# USB-PORT.net
KiCad netlist of a schematic drawn in Altium Designer
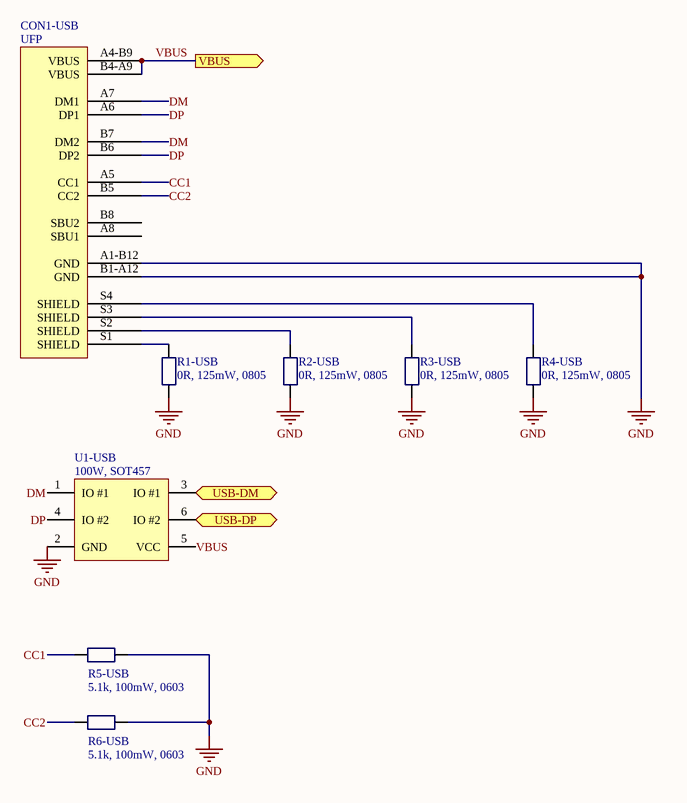
[diagram p0: USB-PORT.SchDoc]

(export (version "E")
  (design (tool "Eeschema 10.0.6"))
  (components
    (comp (ref "CON1-USB")
      (value "UFP")
      (footprint "Molex USB Type-C")
      (description "USB Connector, USB Type C, USB 2.0, Receptacle, 16 Ways, Surface Mount, Right Angle")
      (fields (field (name "MANUFACTURER") "MOLEX"))
      (libsource (lib "SCH-LIB") (part "Molex USB 2.0 Type-C Receptacle"))
    )
    (comp (ref "R1-USB")
      (value "0R, 125mW, 0805")
      (footprint "0805 [2012]")
      (fields (field (name "MANUFACTURER") "MULTICOMP PRO"))
      (libsource (lib "SCH-LIB") (part "Resistor"))
    )
    (comp (ref "R2-USB")
      (value "0R, 125mW, 0805")
      (footprint "0805 [2012]")
      (fields (field (name "MANUFACTURER") "MULTICOMP PRO"))
      (libsource (lib "SCH-LIB") (part "Resistor"))
    )
    (comp (ref "R3-USB")
      (value "0R, 125mW, 0805")
      (footprint "0805 [2012]")
      (fields (field (name "MANUFACTURER") "MULTICOMP PRO"))
      (libsource (lib "SCH-LIB") (part "Resistor"))
    )
    (comp (ref "R4-USB")
      (value "0R, 125mW, 0805")
      (footprint "0805 [2012]")
      (fields (field (name "MANUFACTURER") "MULTICOMP PRO"))
      (libsource (lib "SCH-LIB") (part "Resistor"))
    )
    (comp (ref "R5-USB")
      (value "5.1k, 100mW, 0603")
      (footprint "0603 [1608]")
      (fields (field (name "MANUFACTURER") "YAGEO"))
      (libsource (lib "SCH-LIB") (part "Resistor"))
    )
    (comp (ref "R6-USB")
      (value "5.1k, 100mW, 0603")
      (footprint "0603 [1608]")
      (fields (field (name "MANUFACTURER") "YAGEO"))
      (libsource (lib "SCH-LIB") (part "Resistor"))
    )
    (comp (ref "U1-USB")
      (value "100W, SOT457")
      (footprint "SOT457")
      (fields (field (name "MANUFACTURER") "NEXPERIA"))
      (libsource (lib "SCH-LIB") (part "ESD Protection Device"))
    )
  )
  (nets
    (net (code "1") (name "/CC1") (class "Default")
      (node (ref "CON1-USB") (pin "A5") (pinfunction "CC1_A5") (pintype "passive"))
      (node (ref "R5-USB") (pin "2") (pinfunction "2_2") (pintype "passive"))
    )
    (net (code "2") (name "/CC2") (class "Default")
      (node (ref "CON1-USB") (pin "B5") (pinfunction "CC2_B5") (pintype "passive"))
      (node (ref "R6-USB") (pin "2") (pinfunction "2_2") (pintype "passive"))
    )
    (net (code "3") (name "/DM") (class "Default")
      (node (ref "CON1-USB") (pin "A7") (pinfunction "DM1_A7") (pintype "passive"))
      (node (ref "CON1-USB") (pin "B7") (pinfunction "DM2_B7") (pintype "passive"))
      (node (ref "U1-USB") (pin "1") (pinfunction "IO_#1_1") (pintype "passive"))
    )
    (net (code "4") (name "/DP") (class "Default")
      (node (ref "CON1-USB") (pin "A6") (pinfunction "DP1_A6") (pintype "passive"))
      (node (ref "CON1-USB") (pin "B6") (pinfunction "DP2_B6") (pintype "passive"))
      (node (ref "U1-USB") (pin "4") (pinfunction "IO_#2_4") (pintype "passive"))
    )
    (net (code "5") (name "/USB-DM") (class "Default")
      (node (ref "U1-USB") (pin "3") (pinfunction "IO_#1_3") (pintype "passive"))
    )
    (net (code "6") (name "/USB-DP") (class "Default")
      (node (ref "U1-USB") (pin "6") (pinfunction "IO_#2_6") (pintype "passive"))
    )
    (net (code "7") (name "/VBUS") (class "Default")
      (node (ref "CON1-USB") (pin "A4-B9") (pinfunction "VBUS_A4-B9") (pintype "passive"))
      (node (ref "CON1-USB") (pin "B4-A9") (pinfunction "VBUS_B4-A9") (pintype "passive"))
      (node (ref "U1-USB") (pin "5") (pinfunction "VCC_5") (pintype "passive"))
    )
    (net (code "8") (name "GND") (class "Default")
      (node (ref "CON1-USB") (pin "A1-B12") (pinfunction "GND_A1-B12") (pintype "passive"))
      (node (ref "CON1-USB") (pin "B1-A12") (pinfunction "GND_B1-A12") (pintype "passive"))
      (node (ref "R1-USB") (pin "2") (pinfunction "2_2") (pintype "passive"))
      (node (ref "R2-USB") (pin "2") (pinfunction "2_2") (pintype "passive"))
      (node (ref "R3-USB") (pin "2") (pinfunction "2_2") (pintype "passive"))
      (node (ref "R4-USB") (pin "2") (pinfunction "2_2") (pintype "passive"))
      (node (ref "R5-USB") (pin "1") (pinfunction "1_1") (pintype "passive"))
      (node (ref "R6-USB") (pin "1") (pinfunction "1_1") (pintype "passive"))
      (node (ref "U1-USB") (pin "2") (pinfunction "GND_2") (pintype "passive"))
    )
    (net (code "9") (name "Net-(CON1-USB-SHIELD-PadS1)") (class "Default")
      (node (ref "CON1-USB") (pin "S1") (pinfunction "SHIELD_S1") (pintype "passive"))
      (node (ref "R1-USB") (pin "1") (pinfunction "1_1") (pintype "passive"))
    )
    (net (code "10") (name "Net-(CON1-USB-SHIELD-PadS2)") (class "Default")
      (node (ref "CON1-USB") (pin "S2") (pinfunction "SHIELD_S2") (pintype "passive"))
      (node (ref "R2-USB") (pin "1") (pinfunction "1_1") (pintype "passive"))
    )
    (net (code "11") (name "Net-(CON1-USB-SHIELD-PadS3)") (class "Default")
      (node (ref "CON1-USB") (pin "S3") (pinfunction "SHIELD_S3") (pintype "passive"))
      (node (ref "R3-USB") (pin "1") (pinfunction "1_1") (pintype "passive"))
    )
    (net (code "12") (name "Net-(CON1-USB-SHIELD-PadS4)") (class "Default")
      (node (ref "CON1-USB") (pin "S4") (pinfunction "SHIELD_S4") (pintype "passive"))
      (node (ref "R4-USB") (pin "1") (pinfunction "1_1") (pintype "passive"))
    )
    (net (code "13") (name "unconnected-(CON1-USB-SBU1-PadA8)") (class "Default")
      (node (ref "CON1-USB") (pin "A8") (pinfunction "SBU1_A8") (pintype "passive"))
    )
    (net (code "14") (name "unconnected-(CON1-USB-SBU2-PadB8)") (class "Default")
      (node (ref "CON1-USB") (pin "B8") (pinfunction "SBU2_B8") (pintype "passive"))
    )
  )
)
